# PROC099B_XDS110_Interface_1B.net
KiCad netlist of a schematic drawn in Altium Designer
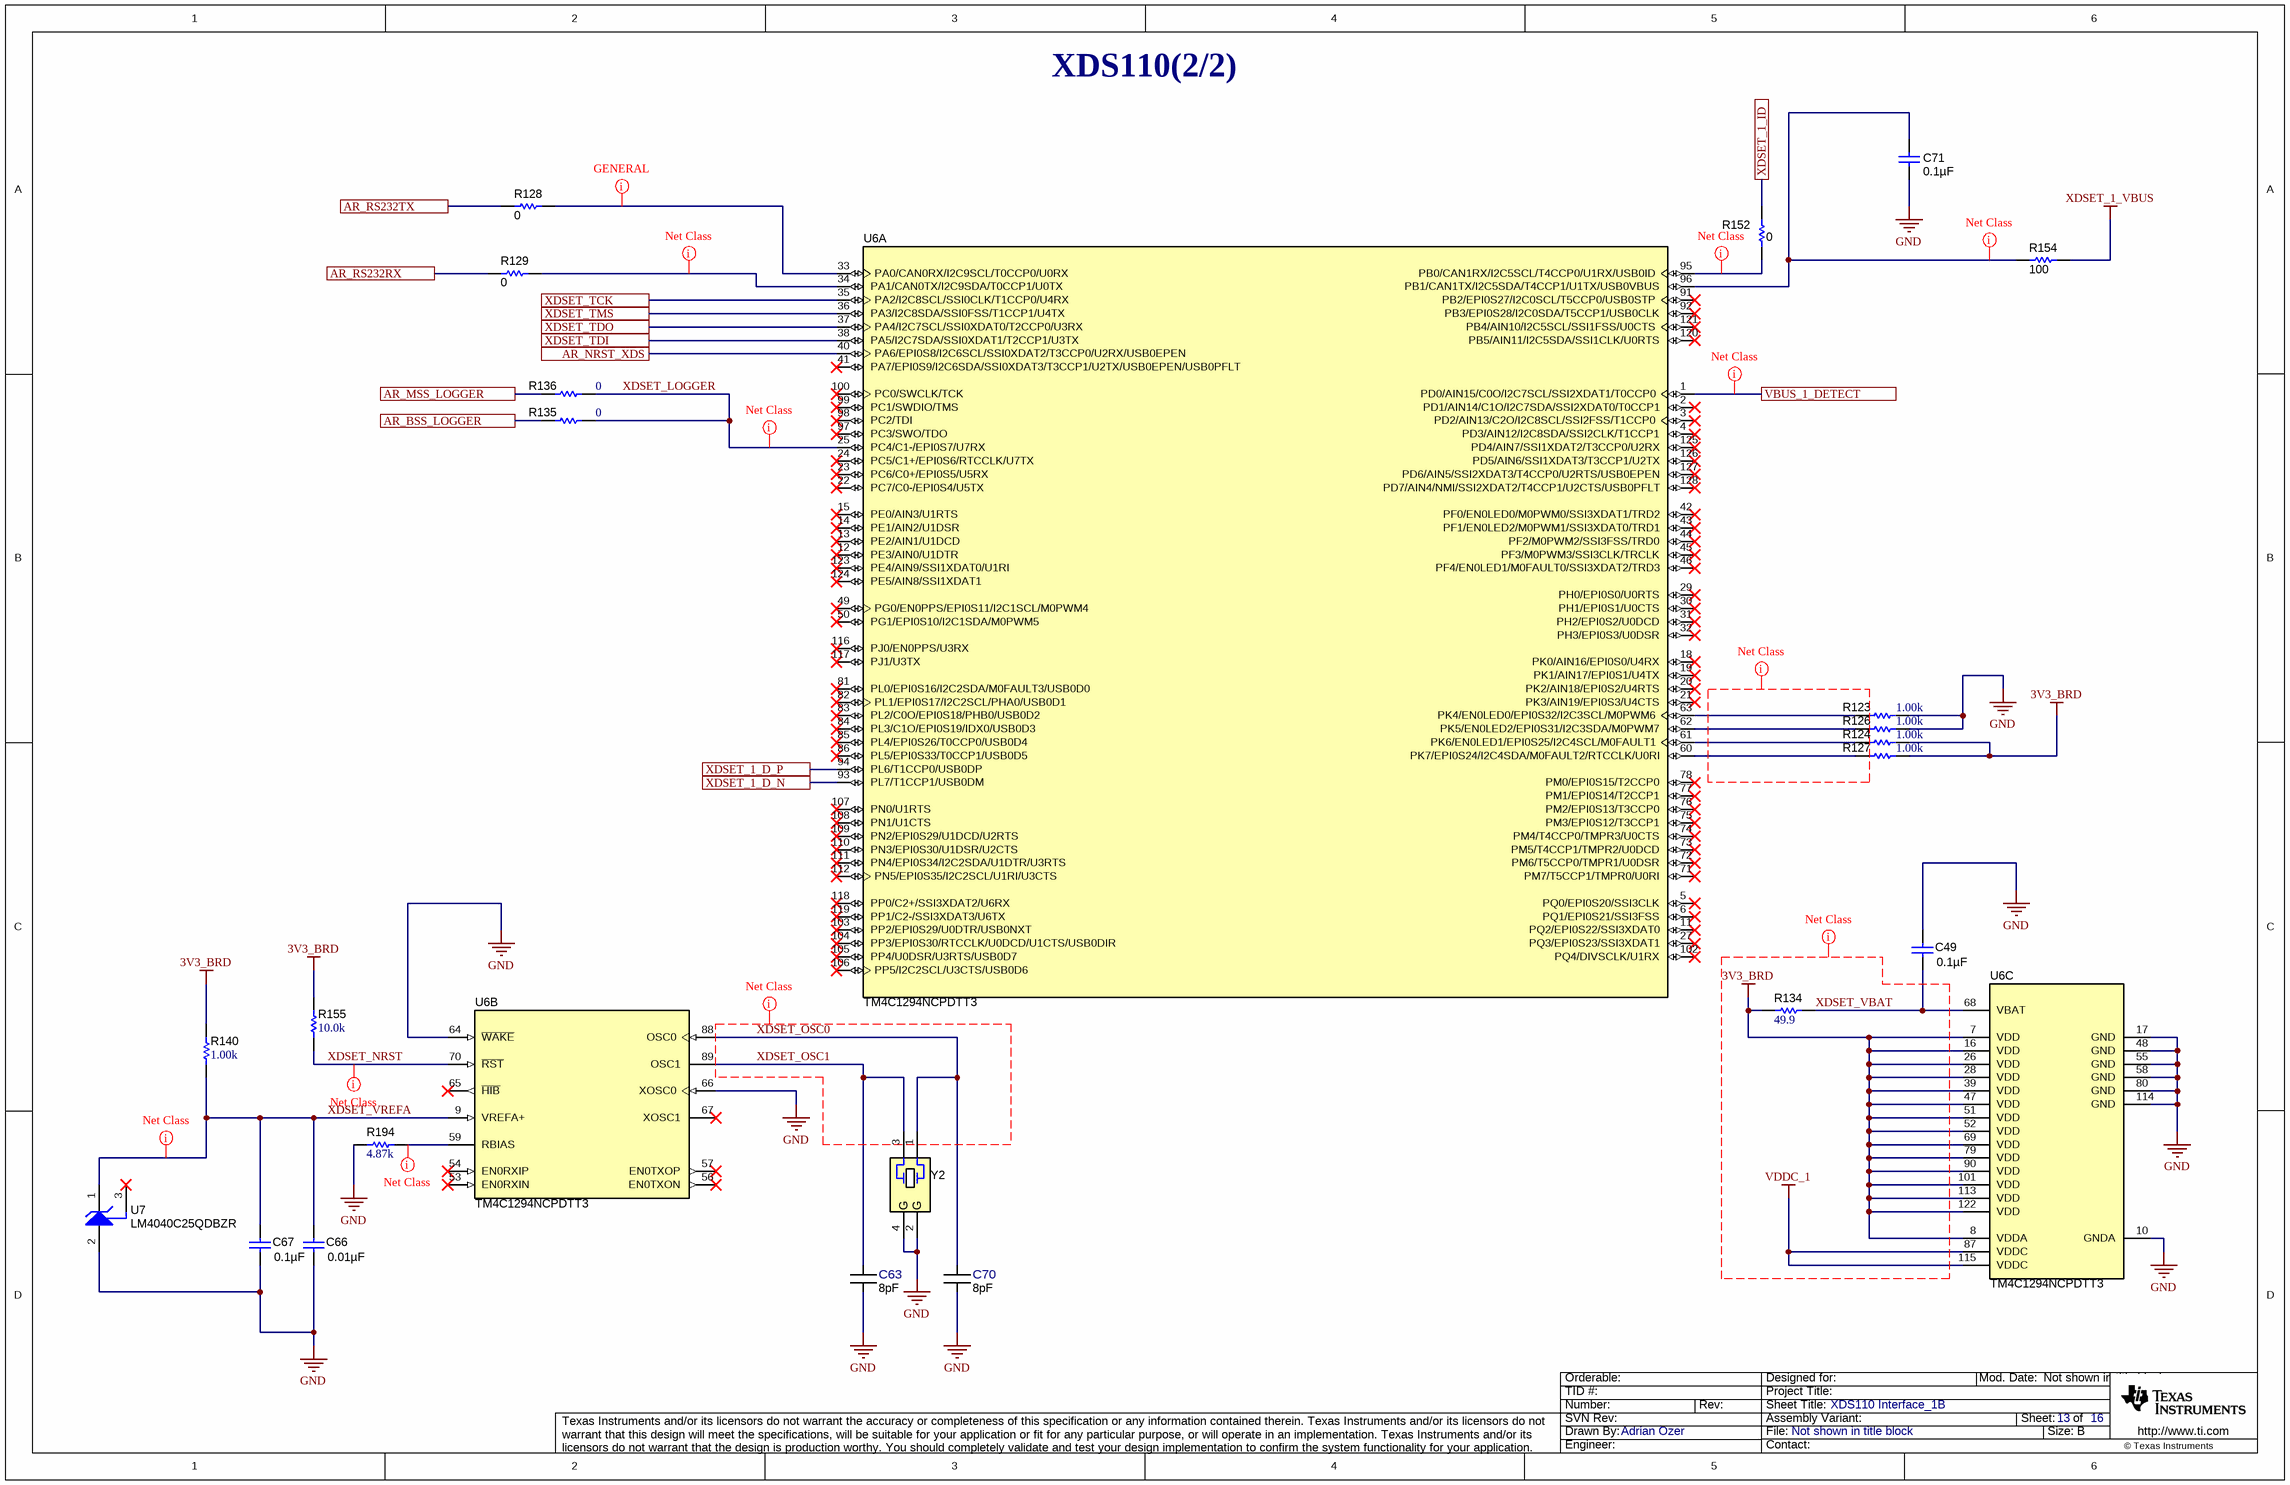
[diagram p0: PROC099B_XDS110 Interface_1B.SchDoc]

(export (version "E")
  (design (tool "Eeschema 10.0.6"))
  (components
    (comp (ref "C49")
      (value "C0402C104K8RACTU")
      (footprint "0402L")
      (description "CAP, CERM, 0.1 µF, 10 V,+/- 10%, X7R, 0402")
      (fields (field (name "MANUFACTURER") "Kemet") (field (name "VALUEDISPLAYED") "0.1µF"))
      (libsource (lib "Altium Vault - TI") (part "CMP-0078241-1"))
    )
    (comp (ref "C63")
      (value "GCM1555C1H8R0DA16D")
      (footprint "FP-GCM1555C1H8R0DA16_0402-MFG")
      (description "Cap Ceramic 8pF 50V C0G 0.5pF SMD 0402 125C Paper T/R")
      (fields (field (name "CAP_F") "8pF") (field (name "MANUFACTURER") "Murata Electronics North America"))
      (libsource (lib "Altium Vault - TI") (part "SYM-B32642B0223J"))
    )
    (comp (ref "C66")
      (value "C0402C103K4RACTU")
      (footprint "0402L")
      (description "CAP, CERM, 0.01 µF, 16 V,+/- 10%, X7R, 0402")
      (fields (field (name "MANUFACTURER") "Kemet") (field (name "VALUEDISPLAYED") "0.01µF"))
      (libsource (lib "Altium Vault - TI") (part "Capacitor"))
    )
    (comp (ref "C67")
      (value "C0402C104K8RACTU")
      (footprint "0402L")
      (description "CAP, CERM, 0.1 µF, 10 V,+/- 10%, X7R, 0402")
      (fields (field (name "MANUFACTURER") "Kemet") (field (name "VALUEDISPLAYED") "0.1µF"))
      (libsource (lib "Altium Vault - TI") (part "Capacitor"))
    )
    (comp (ref "C70")
      (value "GCM1555C1H8R0DA16D")
      (footprint "FP-GCM1555C1H8R0DA16_0402-MFG")
      (description "Cap Ceramic 8pF 50V C0G 0.5pF SMD 0402 125C Paper T/R")
      (fields (field (name "CAP_F") "8pF") (field (name "MANUFACTURER") "Murata Electronics North America"))
      (libsource (lib "Altium Vault - TI") (part "SYM-B32642B0223J"))
    )
    (comp (ref "C71")
      (value "C0402C104K8RACTU")
      (footprint "0402L")
      (description "CAP, CERM, 0.1 µF, 10 V,+/- 10%, X7R, 0402")
      (fields (field (name "MANUFACTURER") "Kemet") (field (name "VALUEDISPLAYED") "0.1µF"))
      (libsource (lib "Altium Vault - TI") (part "Capacitor"))
    )
    (comp (ref "R123")
      (value "CRCW04021K00FKED")
      (footprint "0402L")
      (description "RES, 1.00 k, 1%, 0.063 W, AEC-Q200 Grade 0, 0402")
      (fields (field (name "MANUFACTURER") "Vishay-Dale") (field (name "VALUEDISPLAYED") "1.00k"))
      (libsource (lib "Altium Vault - TI") (part "Resistor"))
    )
    (comp (ref "R124")
      (value "CRCW04021K00FKED")
      (footprint "0402L")
      (description "RES, 1.00 k, 1%, 0.063 W, AEC-Q200 Grade 0, 0402")
      (fields (field (name "MANUFACTURER") "Vishay-Dale") (field (name "VALUEDISPLAYED") "1.00k"))
      (libsource (lib "Altium Vault - TI") (part "Resistor"))
    )
    (comp (ref "R126")
      (value "CRCW04021K00FKED")
      (footprint "0402L")
      (description "RES, 1.00 k, 1%, 0.063 W, AEC-Q200 Grade 0, 0402")
      (fields (field (name "MANUFACTURER") "Vishay-Dale") (field (name "VALUEDISPLAYED") "1.00k"))
      (libsource (lib "Altium Vault - TI") (part "Resistor"))
    )
    (comp (ref "R127")
      (value "CRCW04021K00FKED")
      (footprint "0402L")
      (description "RES, 1.00 k, 1%, 0.063 W, AEC-Q200 Grade 0, 0402")
      (fields (field (name "MANUFACTURER") "Vishay-Dale") (field (name "VALUEDISPLAYED") "1.00k"))
      (libsource (lib "Altium Vault - TI") (part "Resistor"))
    )
    (comp (ref "R128")
      (value "ERJ-2GE0R00X")
      (footprint "0402L")
      (description "RES, 0, 5%, 0.063 W, 0402")
      (fields
        (field (name "MANUFACTURER") "Panasonic")
        (field (name "VALUEDISPLAYED") "0")
        (field (name "PUBLISHER") "Texas Instruments")
      )
      (libsource (lib "Altium Vault - TI") (part "Resistor"))
    )
    (comp (ref "R129")
      (value "ERJ-2GE0R00X")
      (footprint "0402L")
      (description "RES, 0, 5%, 0.063 W, 0402")
      (fields
        (field (name "MANUFACTURER") "Panasonic")
        (field (name "VALUEDISPLAYED") "0")
        (field (name "PUBLISHER") "Texas Instruments")
      )
      (libsource (lib "Altium Vault - TI") (part "Resistor"))
    )
    (comp (ref "R134")
      (value "CRCW040249R9FKED")
      (footprint "0402L")
      (description "RES, 49.9, 1%, 0.063 W, AEC-Q200 Grade 0, 0402")
      (fields (field (name "MANUFACTURER") "Vishay-Dale") (field (name "VALUEDISPLAYED") "49.9"))
      (libsource (lib "Altium Vault - TI") (part "Resistor"))
    )
    (comp (ref "R135")
      (value "CRCW02010000Z0ED")
      (footprint "0201_Silk")
      (description "RES, 0, 5%, 0.05 W, 0201")
      (fields (field (name "MANUFACTURER") "Vishay-Dale") (field (name "VALUEDISPLAYED") "0"))
      (libsource (lib "Altium Vault - TI") (part "Resistor"))
    )
    (comp (ref "R136")
      (value "CRCW02010000Z0ED")
      (footprint "0201_Silk")
      (description "RES, 0, 5%, 0.05 W, 0201")
      (fields (field (name "MANUFACTURER") "Vishay-Dale") (field (name "VALUEDISPLAYED") "0"))
      (libsource (lib "Altium Vault - TI") (part "Resistor"))
    )
    (comp (ref "R140")
      (value "CRCW04021K00FKED")
      (footprint "0402L")
      (description "RES, 1.00 k, 1%, 0.063 W, AEC-Q200 Grade 0, 0402")
      (fields (field (name "MANUFACTURER") "Vishay-Dale") (field (name "VALUEDISPLAYED") "1.00k"))
      (libsource (lib "Altium Vault - TI") (part "Resistor"))
    )
    (comp (ref "R152")
      (value "ERJ-2GE0R00X")
      (footprint "0402L")
      (description "RES, 0, 5%, 0.063 W, 0402")
      (fields
        (field (name "MANUFACTURER") "Panasonic")
        (field (name "VALUEDISPLAYED") "0")
        (field (name "PUBLISHER") "Texas Instruments")
      )
      (libsource (lib "Altium Vault - TI") (part "Resistor"))
    )
    (comp (ref "R154")
      (value "ERJ-2GEJ101X")
      (footprint "0402L")
      (description "RES, 100, 5%, 0.1 W, AEC-Q200 Grade 0, 0402")
      (fields
        (field (name "MANUFACTURER") "Panasonic")
        (field (name "VALUEDISPLAYED") "100")
        (field (name "PUBLISHER") "Texas Instruments")
      )
      (libsource (lib "Altium Vault - TI") (part "Resistor"))
    )
    (comp (ref "R155")
      (value "CRCW040210K0FKED")
      (footprint "0402L")
      (description "RES, 10.0 k, 1%, 0.063 W, AEC-Q200 Grade 0, 0402")
      (fields (field (name "MANUFACTURER") "Vishay-Dale") (field (name "VALUEDISPLAYED") "10.0k"))
      (libsource (lib "Altium Vault - TI") (part "Resistor"))
    )
    (comp (ref "R194")
      (value "CRCW04024K87FKED")
      (footprint "0402L")
      (description "RES, 4.87 k, 1%, 0.063 W, AEC-Q200 Grade 0, 0402")
      (fields (field (name "MANUFACTURER") "Vishay-Dale") (field (name "VALUEDISPLAYED") "4.87k"))
      (libsource (lib "Altium Vault - TI") (part "Resistor"))
    )
    (comp (ref "U6")
      (value "TM4C1294NCPDTT3")
      (footprint "PDT0128A")
      (fields (field (name "PARTNUMBER") "TM4C1294NCPDTT3") (field (name "MANUFACTURER") "Texas Instruments"))
      (libsource (lib "Altium Vault - TI") (part "TI-TM4C1294NCPDT-128"))
    )
    (comp (ref "U7")
      (value "LM4040C25QDBZR")
      (footprint "DBZ0003A_N")
      (fields (field (name "MANUFACTURER") "Texas Instruments") (field (name "PARTNUMBER") "LM4040C25QDBZR"))
      (libsource (lib "Altium Vault - TI") (part "TI-LM4040C25DBZ3"))
    )
    (comp (ref "Y2")
      (value "NX3225SA-16.000M-STD-CRS-2")
      (footprint "NDK_NX3225SA")
      (description "Crystal, 16 MHz, 15 ppm, 8 pF, AEC-Q200 Grade 1, SMD")
      (fields (field (name "MANUFACTURER") "NDK"))
      (libsource (lib "Altium Vault - TI") (part "CMP-0078214-2"))
    )
  )
  (nets
    (net (code "1") (name "/AR_BSS_LOGGER") (class "Default")
      (node (ref "R135") (pin "1") (pinfunction "1_1") (pintype "passive"))
    )
    (net (code "2") (name "/AR_MSS_LOGGER") (class "Default")
      (node (ref "R136") (pin "1") (pinfunction "1_1") (pintype "passive"))
    )
    (net (code "3") (name "/AR_NRST_XDS") (class "Default")
      (node (ref "U6") (pin "40") (pinfunction "PA6/EPI0S8/I2C6SCL/SSI0XDAT2/T3CCP0/U2RX/USB0EPEN_40") (pintype "bidirectional"))
    )
    (net (code "4") (name "/AR_RS232RX") (class "Default")
      (node (ref "R129") (pin "1") (pinfunction "1_1") (pintype "passive"))
    )
    (net (code "5") (name "/AR_RS232TX") (class "Default")
      (node (ref "R128") (pin "1") (pinfunction "1_1") (pintype "passive"))
    )
    (net (code "6") (name "/VBUS_1_DETECT") (class "Default")
      (node (ref "U6") (pin "1") (pinfunction "PD0/AIN15/C0O/I2C7SCL/SSI2XDAT1/T0CCP0_1") (pintype "bidirectional"))
    )
    (net (code "7") (name "/XDSET_1_D_N") (class "Default")
      (node (ref "U6") (pin "93") (pinfunction "PL7/T1CCP1/USB0DM_93") (pintype "bidirectional"))
    )
    (net (code "8") (name "/XDSET_1_D_P") (class "Default")
      (node (ref "U6") (pin "94") (pinfunction "PL6/T1CCP0/USB0DP_94") (pintype "bidirectional"))
    )
    (net (code "9") (name "/XDSET_1_ID") (class "Default")
      (node (ref "R152") (pin "2") (pinfunction "2_2") (pintype "passive"))
    )
    (net (code "10") (name "/XDSET_LOGGER") (class "Default")
      (node (ref "R135") (pin "2") (pinfunction "2_2") (pintype "passive"))
      (node (ref "R136") (pin "2") (pinfunction "2_2") (pintype "passive"))
      (node (ref "U6") (pin "25") (pinfunction "PC4/C1-/EPI0S7/U7RX_25") (pintype "bidirectional"))
    )
    (net (code "11") (name "/XDSET_NRST") (class "Default")
      (node (ref "R155") (pin "1") (pinfunction "1_1") (pintype "passive"))
      (node (ref "U6") (pin "70") (pinfunction "~{RST}_70") (pintype "input"))
    )
    (net (code "12") (name "/XDSET_OSC0") (class "Default")
      (node (ref "C70") (pin "1") (pinfunction "1_1") (pintype "passive"))
      (node (ref "U6") (pin "88") (pinfunction "OSC0_88") (pintype "input"))
      (node (ref "Y2") (pin "1") (pinfunction "1_1") (pintype "passive"))
    )
    (net (code "13") (name "/XDSET_OSC1") (class "Default")
      (node (ref "C63") (pin "1") (pinfunction "1_1") (pintype "passive"))
      (node (ref "U6") (pin "89") (pinfunction "OSC1_89") (pintype "passive"))
      (node (ref "Y2") (pin "3") (pinfunction "3_3") (pintype "passive"))
    )
    (net (code "14") (name "/XDSET_TCK") (class "Default")
      (node (ref "U6") (pin "35") (pinfunction "PA2/I2C8SCL/SSI0CLK/T1CCP0/U4RX_35") (pintype "bidirectional"))
    )
    (net (code "15") (name "/XDSET_TDI") (class "Default")
      (node (ref "U6") (pin "38") (pinfunction "PA5/I2C7SDA/SSI0XDAT1/T2CCP1/U3TX_38") (pintype "bidirectional"))
    )
    (net (code "16") (name "/XDSET_TDO") (class "Default")
      (node (ref "U6") (pin "37") (pinfunction "PA4/I2C7SCL/SSI0XDAT0/T2CCP0/U3RX_37") (pintype "bidirectional"))
    )
    (net (code "17") (name "/XDSET_TMS") (class "Default")
      (node (ref "U6") (pin "36") (pinfunction "PA3/I2C8SDA/SSI0FSS/T1CCP1/U4TX_36") (pintype "bidirectional"))
    )
    (net (code "18") (name "/XDSET_VBAT") (class "Default")
      (node (ref "C49") (pin "2") (pinfunction "2_2") (pintype "passive"))
      (node (ref "R134") (pin "1") (pinfunction "1_1") (pintype "passive"))
      (node (ref "U6") (pin "68") (pinfunction "VBAT_68") (pintype "power_in"))
    )
    (net (code "19") (name "/XDSET_VREFA") (class "Default")
      (node (ref "C66") (pin "2") (pinfunction "2_2") (pintype "passive"))
      (node (ref "C67") (pin "2") (pinfunction "2_2") (pintype "passive"))
      (node (ref "R140") (pin "1") (pinfunction "1_1") (pintype "passive"))
      (node (ref "U6") (pin "9") (pinfunction "VREFA+_9") (pintype "input"))
      (node (ref "U7") (pin "1") (pinfunction "CATHODE_1") (pintype "passive"))
    )
    (net (code "20") (name "3V3_BRD") (class "Default")
      (node (ref "R124") (pin "2") (pinfunction "2_2") (pintype "passive"))
      (node (ref "R127") (pin "2") (pinfunction "2_2") (pintype "passive"))
      (node (ref "R134") (pin "2") (pinfunction "2_2") (pintype "passive"))
      (node (ref "R140") (pin "2") (pinfunction "2_2") (pintype "passive"))
      (node (ref "R155") (pin "2") (pinfunction "2_2") (pintype "passive"))
      (node (ref "U6") (pin "101") (pinfunction "VDD_101") (pintype "power_in"))
      (node (ref "U6") (pin "113") (pinfunction "VDD_113") (pintype "power_in"))
      (node (ref "U6") (pin "122") (pinfunction "VDD_122") (pintype "power_in"))
      (node (ref "U6") (pin "16") (pinfunction "VDD_16") (pintype "power_in"))
      (node (ref "U6") (pin "26") (pinfunction "VDD_26") (pintype "power_in"))
      (node (ref "U6") (pin "28") (pinfunction "VDD_28") (pintype "power_in"))
      (node (ref "U6") (pin "39") (pinfunction "VDD_39") (pintype "power_in"))
      (node (ref "U6") (pin "47") (pinfunction "VDD_47") (pintype "power_in"))
      (node (ref "U6") (pin "51") (pinfunction "VDD_51") (pintype "power_in"))
      (node (ref "U6") (pin "52") (pinfunction "VDD_52") (pintype "power_in"))
      (node (ref "U6") (pin "69") (pinfunction "VDD_69") (pintype "power_in"))
      (node (ref "U6") (pin "7") (pinfunction "VDD_7") (pintype "power_in"))
      (node (ref "U6") (pin "79") (pinfunction "VDD_79") (pintype "power_in"))
      (node (ref "U6") (pin "8") (pinfunction "VDDA_8") (pintype "power_in"))
      (node (ref "U6") (pin "90") (pinfunction "VDD_90") (pintype "power_in"))
    )
    (net (code "21") (name "GND") (class "Default")
      (node (ref "C49") (pin "1") (pinfunction "1_1") (pintype "passive"))
      (node (ref "C63") (pin "2") (pinfunction "2_2") (pintype "passive"))
      (node (ref "C66") (pin "1") (pinfunction "1_1") (pintype "passive"))
      (node (ref "C67") (pin "1") (pinfunction "1_1") (pintype "passive"))
      (node (ref "C70") (pin "2") (pinfunction "2_2") (pintype "passive"))
      (node (ref "C71") (pin "1") (pinfunction "1_1") (pintype "passive"))
      (node (ref "R123") (pin "2") (pinfunction "2_2") (pintype "passive"))
      (node (ref "R126") (pin "2") (pinfunction "2_2") (pintype "passive"))
      (node (ref "R194") (pin "1") (pinfunction "1_1") (pintype "passive"))
      (node (ref "U6") (pin "10") (pinfunction "GNDA_10") (pintype "power_in"))
      (node (ref "U6") (pin "114") (pinfunction "GND_114") (pintype "power_in"))
      (node (ref "U6") (pin "17") (pinfunction "GND_17") (pintype "power_in"))
      (node (ref "U6") (pin "48") (pinfunction "GND_48") (pintype "power_in"))
      (node (ref "U6") (pin "55") (pinfunction "GND_55") (pintype "power_in"))
      (node (ref "U6") (pin "58") (pinfunction "GND_58") (pintype "power_in"))
      (node (ref "U6") (pin "64") (pinfunction "~{WAKE}_64") (pintype "input"))
      (node (ref "U6") (pin "66") (pinfunction "XOSC0_66") (pintype "input"))
      (node (ref "U6") (pin "80") (pinfunction "GND_80") (pintype "power_in"))
      (node (ref "U7") (pin "2") (pinfunction "ANODE_2") (pintype "passive"))
      (node (ref "Y2") (pin "2") (pinfunction "GND_2") (pintype "power_in"))
      (node (ref "Y2") (pin "4") (pinfunction "GND_4") (pintype "power_in"))
    )
    (net (code "22") (name "Net-(U6A-PA0{slash}CAN0RX{slash}I2C9SCL{slash}T0CCP0{slash}U0RX)") (class "Default")
      (node (ref "R128") (pin "2") (pinfunction "2_2") (pintype "passive"))
      (node (ref "U6") (pin "33") (pinfunction "PA0/CAN0RX/I2C9SCL/T0CCP0/U0RX_33") (pintype "bidirectional"))
    )
    (net (code "23") (name "Net-(U6A-PA1{slash}CAN0TX{slash}I2C9SDA{slash}T0CCP1{slash}U0TX)") (class "Default")
      (node (ref "R129") (pin "2") (pinfunction "2_2") (pintype "passive"))
      (node (ref "U6") (pin "34") (pinfunction "PA1/CAN0TX/I2C9SDA/T0CCP1/U0TX_34") (pintype "bidirectional"))
    )
    (net (code "24") (name "Net-(U6A-PB0{slash}CAN1RX{slash}I2C5SCL{slash}T4CCP0{slash}U1RX{slash}USB0ID)") (class "Default")
      (node (ref "R152") (pin "1") (pinfunction "1_1") (pintype "passive"))
      (node (ref "U6") (pin "95") (pinfunction "PB0/CAN1RX/I2C5SCL/T4CCP0/U1RX/USB0ID_95") (pintype "bidirectional"))
    )
    (net (code "25") (name "Net-(U6A-PB1{slash}CAN1TX{slash}I2C5SDA{slash}T4CCP1{slash}U1TX{slash}USB0VBUS)") (class "Default")
      (node (ref "C71") (pin "2") (pinfunction "2_2") (pintype "passive"))
      (node (ref "R154") (pin "1") (pinfunction "1_1") (pintype "passive"))
      (node (ref "U6") (pin "96") (pinfunction "PB1/CAN1TX/I2C5SDA/T4CCP1/U1TX/USB0VBUS_96") (pintype "bidirectional"))
    )
    (net (code "26") (name "Net-(U6A-PK4{slash}EN0LED0{slash}EPI0S32{slash}I2C3SCL{slash}M0PWM6)") (class "Default")
      (node (ref "R123") (pin "1") (pinfunction "1_1") (pintype "passive"))
      (node (ref "U6") (pin "63") (pinfunction "PK4/EN0LED0/EPI0S32/I2C3SCL/M0PWM6_63") (pintype "bidirectional"))
    )
    (net (code "27") (name "Net-(U6A-PK5{slash}EN0LED2{slash}EPI0S31{slash}I2C3SDA{slash}M0PWM7)") (class "Default")
      (node (ref "R126") (pin "1") (pinfunction "1_1") (pintype "passive"))
      (node (ref "U6") (pin "62") (pinfunction "PK5/EN0LED2/EPI0S31/I2C3SDA/M0PWM7_62") (pintype "bidirectional"))
    )
    (net (code "28") (name "Net-(U6A-PK6{slash}EN0LED1{slash}EPI0S25{slash}I2C4SCL{slash}M0FAULT1)") (class "Default")
      (node (ref "R124") (pin "1") (pinfunction "1_1") (pintype "passive"))
      (node (ref "U6") (pin "61") (pinfunction "PK6/EN0LED1/EPI0S25/I2C4SCL/M0FAULT1_61") (pintype "bidirectional"))
    )
    (net (code "29") (name "Net-(U6A-PK7{slash}EPI0S24{slash}I2C4SDA{slash}M0FAULT2{slash}RTCCLK{slash}U0RI)") (class "Default")
      (node (ref "R127") (pin "1") (pinfunction "1_1") (pintype "passive"))
      (node (ref "U6") (pin "60") (pinfunction "PK7/EPI0S24/I2C4SDA/M0FAULT2/RTCCLK/U0RI_60") (pintype "bidirectional"))
    )
    (net (code "30") (name "Net-(U6B-RBIAS)") (class "Default")
      (node (ref "R194") (pin "2") (pinfunction "2_2") (pintype "passive"))
      (node (ref "U6") (pin "59") (pinfunction "RBIAS_59") (pintype "passive"))
    )
    (net (code "31") (name "VDDC_1") (class "Default")
      (node (ref "U6") (pin "115") (pinfunction "VDDC_115") (pintype "power_in"))
      (node (ref "U6") (pin "87") (pinfunction "VDDC_87") (pintype "power_in"))
    )
    (net (code "32") (name "XDSET_1_VBUS") (class "Default")
      (node (ref "R154") (pin "2") (pinfunction "2_2") (pintype "passive"))
    )
    (net (code "33") (name "unconnected-(U6A-PA7{slash}EPI0S9{slash}I2C6SDA{slash}SSI0XDAT3{slash}T3CCP1{slash}U2TX{slash}USB0EPEN{slash}USB0PFLT-Pad41)") (class "Default")
      (node (ref "U6") (pin "41") (pinfunction "PA7/EPI0S9/I2C6SDA/SSI0XDAT3/T3CCP1/U2TX/USB0EPEN/USB0PFLT_41") (pintype "bidirectional+no_connect"))
    )
    (net (code "34") (name "unconnected-(U6A-PB2{slash}EPI0S27{slash}I2C0SCL{slash}T5CCP0{slash}USB0STP-Pad91)") (class "Default")
      (node (ref "U6") (pin "91") (pinfunction "PB2/EPI0S27/I2C0SCL/T5CCP0/USB0STP_91") (pintype "bidirectional+no_connect"))
    )
    (net (code "35") (name "unconnected-(U6A-PB3{slash}EPI0S28{slash}I2C0SDA{slash}T5CCP1{slash}USB0CLK-Pad92)") (class "Default")
      (node (ref "U6") (pin "92") (pinfunction "PB3/EPI0S28/I2C0SDA/T5CCP1/USB0CLK_92") (pintype "bidirectional+no_connect"))
    )
    (net (code "36") (name "unconnected-(U6A-PB4{slash}AIN10{slash}I2C5SCL{slash}SSI1FSS{slash}U0CTS-Pad121)") (class "Default")
      (node (ref "U6") (pin "121") (pinfunction "PB4/AIN10/I2C5SCL/SSI1FSS/U0CTS_121") (pintype "bidirectional+no_connect"))
    )
    (net (code "37") (name "unconnected-(U6A-PB5{slash}AIN11{slash}I2C5SDA{slash}SSI1CLK{slash}U0RTS-Pad120)") (class "Default")
      (node (ref "U6") (pin "120") (pinfunction "PB5/AIN11/I2C5SDA/SSI1CLK/U0RTS_120") (pintype "bidirectional+no_connect"))
    )
    (net (code "38") (name "unconnected-(U6A-PC0{slash}SWCLK{slash}TCK-Pad100)") (class "Default")
      (node (ref "U6") (pin "100") (pinfunction "PC0/SWCLK/TCK_100") (pintype "bidirectional+no_connect"))
    )
    (net (code "39") (name "unconnected-(U6A-PC1{slash}SWDIO{slash}TMS-Pad99)") (class "Default")
      (node (ref "U6") (pin "99") (pinfunction "PC1/SWDIO/TMS_99") (pintype "bidirectional+no_connect"))
    )
    (net (code "40") (name "unconnected-(U6A-PC2{slash}TDI-Pad98)") (class "Default")
      (node (ref "U6") (pin "98") (pinfunction "PC2/TDI_98") (pintype "bidirectional+no_connect"))
    )
    (net (code "41") (name "unconnected-(U6A-PC3{slash}SWO{slash}TDO-Pad97)") (class "Default")
      (node (ref "U6") (pin "97") (pinfunction "PC3/SWO/TDO_97") (pintype "bidirectional+no_connect"))
    )
    (net (code "42") (name "unconnected-(U6A-PC5{slash}C1+{slash}EPI0S6{slash}RTCCLK{slash}U7TX-Pad24)") (class "Default")
      (node (ref "U6") (pin "24") (pinfunction "PC5/C1+/EPI0S6/RTCCLK/U7TX_24") (pintype "bidirectional+no_connect"))
    )
    (net (code "43") (name "unconnected-(U6A-PC6{slash}C0+{slash}EPI0S5{slash}U5RX-Pad23)") (class "Default")
      (node (ref "U6") (pin "23") (pinfunction "PC6/C0+/EPI0S5/U5RX_23") (pintype "bidirectional+no_connect"))
    )
    (net (code "44") (name "unconnected-(U6A-PC7{slash}C0-{slash}EPI0S4{slash}U5TX-Pad22)") (class "Default")
      (node (ref "U6") (pin "22") (pinfunction "PC7/C0-/EPI0S4/U5TX_22") (pintype "bidirectional+no_connect"))
    )
    (net (code "45") (name "unconnected-(U6A-PD1{slash}AIN14{slash}C1O{slash}I2C7SDA{slash}SSI2XDAT0{slash}T0CCP1-Pad2)") (class "Default")
      (node (ref "U6") (pin "2") (pinfunction "PD1/AIN14/C1O/I2C7SDA/SSI2XDAT0/T0CCP1_2") (pintype "bidirectional+no_connect"))
    )
    (net (code "46") (name "unconnected-(U6A-PD2{slash}AIN13{slash}C2O{slash}I2C8SCL{slash}SSI2FSS{slash}T1CCP0-Pad3)") (class "Default")
      (node (ref "U6") (pin "3") (pinfunction "PD2/AIN13/C2O/I2C8SCL/SSI2FSS/T1CCP0_3") (pintype "bidirectional+no_connect"))
    )
    (net (code "47") (name "unconnected-(U6A-PD3{slash}AIN12{slash}I2C8SDA{slash}SSI2CLK{slash}T1CCP1-Pad4)") (class "Default")
      (node (ref "U6") (pin "4") (pinfunction "PD3/AIN12/I2C8SDA/SSI2CLK/T1CCP1_4") (pintype "bidirectional+no_connect"))
    )
    (net (code "48") (name "unconnected-(U6A-PD4{slash}AIN7{slash}SSI1XDAT2{slash}T3CCP0{slash}U2RX-Pad125)") (class "Default")
      (node (ref "U6") (pin "125") (pinfunction "PD4/AIN7/SSI1XDAT2/T3CCP0/U2RX_125") (pintype "bidirectional+no_connect"))
    )
    (net (code "49") (name "unconnected-(U6A-PD5{slash}AIN6{slash}SSI1XDAT3{slash}T3CCP1{slash}U2TX-Pad126)") (class "Default")
      (node (ref "U6") (pin "126") (pinfunction "PD5/AIN6/SSI1XDAT3/T3CCP1/U2TX_126") (pintype "bidirectional+no_connect"))
    )
    (net (code "50") (name "unconnected-(U6A-PD6{slash}AIN5{slash}SSI2XDAT3{slash}T4CCP0{slash}U2RTS{slash}USB0EPEN-Pad127)") (class "Default")
      (node (ref "U6") (pin "127") (pinfunction "PD6/AIN5/SSI2XDAT3/T4CCP0/U2RTS/USB0EPEN_127") (pintype "bidirectional+no_connect"))
    )
    (net (code "51") (name "unconnected-(U6A-PD7{slash}AIN4{slash}NMI{slash}SSI2XDAT2{slash}T4CCP1{slash}U2CTS{slash}USB0PFLT-Pad128)") (class "Default")
      (node (ref "U6") (pin "128") (pinfunction "PD7/AIN4/NMI/SSI2XDAT2/T4CCP1/U2CTS/USB0PFLT_128") (pintype "bidirectional+no_connect"))
    )
    (net (code "52") (name "unconnected-(U6A-PE0{slash}AIN3{slash}U1RTS-Pad15)") (class "Default")
      (node (ref "U6") (pin "15") (pinfunction "PE0/AIN3/U1RTS_15") (pintype "bidirectional+no_connect"))
    )
    (net (code "53") (name "unconnected-(U6A-PE1{slash}AIN2{slash}U1DSR-Pad14)") (class "Default")
      (node (ref "U6") (pin "14") (pinfunction "PE1/AIN2/U1DSR_14") (pintype "bidirectional+no_connect"))
    )
    (net (code "54") (name "unconnected-(U6A-PE2{slash}AIN1{slash}U1DCD-Pad13)") (class "Default")
      (node (ref "U6") (pin "13") (pinfunction "PE2/AIN1/U1DCD_13") (pintype "bidirectional+no_connect"))
    )
    (net (code "55") (name "unconnected-(U6A-PE3{slash}AIN0{slash}U1DTR-Pad12)") (class "Default")
      (node (ref "U6") (pin "12") (pinfunction "PE3/AIN0/U1DTR_12") (pintype "bidirectional+no_connect"))
    )
    (net (code "56") (name "unconnected-(U6A-PE4{slash}AIN9{slash}SSI1XDAT0{slash}U1RI-Pad123)") (class "Default")
      (node (ref "U6") (pin "123") (pinfunction "PE4/AIN9/SSI1XDAT0/U1RI_123") (pintype "bidirectional+no_connect"))
    )
    (net (code "57") (name "unconnected-(U6A-PE5{slash}AIN8{slash}SSI1XDAT1-Pad124)") (class "Default")
      (node (ref "U6") (pin "124") (pinfunction "PE5/AIN8/SSI1XDAT1_124") (pintype "bidirectional+no_connect"))
    )
    (net (code "58") (name "unconnected-(U6A-PF0{slash}EN0LED0{slash}M0PWM0{slash}SSI3XDAT1{slash}TRD2-Pad42)") (class "Default")
      (node (ref "U6") (pin "42") (pinfunction "PF0/EN0LED0/M0PWM0/SSI3XDAT1/TRD2_42") (pintype "bidirectional+no_connect"))
    )
    (net (code "59") (name "unconnected-(U6A-PF1{slash}EN0LED2{slash}M0PWM1{slash}SSI3XDAT0{slash}TRD1-Pad43)") (class "Default")
      (node (ref "U6") (pin "43") (pinfunction "PF1/EN0LED2/M0PWM1/SSI3XDAT0/TRD1_43") (pintype "bidirectional+no_connect"))
    )
    (net (code "60") (name "unconnected-(U6A-PF2{slash}M0PWM2{slash}SSI3FSS{slash}TRD0-Pad44)") (class "Default")
      (node (ref "U6") (pin "44") (pinfunction "PF2/M0PWM2/SSI3FSS/TRD0_44") (pintype "bidirectional+no_connect"))
    )
    (net (code "61") (name "unconnected-(U6A-PF3{slash}M0PWM3{slash}SSI3CLK{slash}TRCLK-Pad45)") (class "Default")
      (node (ref "U6") (pin "45") (pinfunction "PF3/M0PWM3/SSI3CLK/TRCLK_45") (pintype "bidirectional+no_connect"))
    )
    (net (code "62") (name "unconnected-(U6A-PF4{slash}EN0LED1{slash}M0FAULT0{slash}SSI3XDAT2{slash}TRD3-Pad46)") (class "Default")
      (node (ref "U6") (pin "46") (pinfunction "PF4/EN0LED1/M0FAULT0/SSI3XDAT2/TRD3_46") (pintype "bidirectional+no_connect"))
    )
    (net (code "63") (name "unconnected-(U6A-PG0{slash}EN0PPS{slash}EPI0S11{slash}I2C1SCL{slash}M0PWM4-Pad49)") (class "Default")
      (node (ref "U6") (pin "49") (pinfunction "PG0/EN0PPS/EPI0S11/I2C1SCL/M0PWM4_49") (pintype "bidirectional+no_connect"))
    )
    (net (code "64") (name "unconnected-(U6A-PG1{slash}EPI0S10{slash}I2C1SDA{slash}M0PWM5-Pad50)") (class "Default")
      (node (ref "U6") (pin "50") (pinfunction "PG1/EPI0S10/I2C1SDA/M0PWM5_50") (pintype "bidirectional+no_connect"))
    )
    (net (code "65") (name "unconnected-(U6A-PH0{slash}EPI0S0{slash}U0RTS-Pad29)") (class "Default")
      (node (ref "U6") (pin "29") (pinfunction "PH0/EPI0S0/U0RTS_29") (pintype "bidirectional+no_connect"))
    )
    (net (code "66") (name "unconnected-(U6A-PH1{slash}EPI0S1{slash}U0CTS-Pad30)") (class "Default")
      (node (ref "U6") (pin "30") (pinfunction "PH1/EPI0S1/U0CTS_30") (pintype "bidirectional+no_connect"))
    )
    (net (code "67") (name "unconnected-(U6A-PH2{slash}EPI0S2{slash}U0DCD-Pad31)") (class "Default")
      (node (ref "U6") (pin "31") (pinfunction "PH2/EPI0S2/U0DCD_31") (pintype "bidirectional+no_connect"))
    )
    (net (code "68") (name "unconnected-(U6A-PH3{slash}EPI0S3{slash}U0DSR-Pad32)") (class "Default")
      (node (ref "U6") (pin "32") (pinfunction "PH3/EPI0S3/U0DSR_32") (pintype "bidirectional+no_connect"))
    )
    (net (code "69") (name "unconnected-(U6A-PJ0{slash}EN0PPS{slash}U3RX-Pad116)") (class "Default")
      (node (ref "U6") (pin "116") (pinfunction "PJ0/EN0PPS/U3RX_116") (pintype "bidirectional+no_connect"))
    )
    (net (code "70") (name "unconnected-(U6A-PJ1{slash}U3TX-Pad117)") (class "Default")
      (node (ref "U6") (pin "117") (pinfunction "PJ1/U3TX_117") (pintype "bidirectional+no_connect"))
    )
    (net (code "71") (name "unconnected-(U6A-PK0{slash}AIN16{slash}EPI0S0{slash}U4RX-Pad18)") (class "Default")
      (node (ref "U6") (pin "18") (pinfunction "PK0/AIN16/EPI0S0/U4RX_18") (pintype "bidirectional+no_connect"))
    )
    (net (code "72") (name "unconnected-(U6A-PK1{slash}AIN17{slash}EPI0S1{slash}U4TX-Pad19)") (class "Default")
      (node (ref "U6") (pin "19") (pinfunction "PK1/AIN17/EPI0S1/U4TX_19") (pintype "bidirectional+no_connect"))
    )
    (net (code "73") (name "unconnected-(U6A-PK2{slash}AIN18{slash}EPI0S2{slash}U4RTS-Pad20)") (class "Default")
      (node (ref "U6") (pin "20") (pinfunction "PK2/AIN18/EPI0S2/U4RTS_20") (pintype "bidirectional+no_connect"))
    )
    (net (code "74") (name "unconnected-(U6A-PK3{slash}AIN19{slash}EPI0S3{slash}U4CTS-Pad21)") (class "Default")
      (node (ref "U6") (pin "21") (pinfunction "PK3/AIN19/EPI0S3/U4CTS_21") (pintype "bidirectional+no_connect"))
    )
    (net (code "75") (name "unconnected-(U6A-PL0{slash}EPI0S16{slash}I2C2SDA{slash}M0FAULT3{slash}USB0D0-Pad81)") (class "Default")
      (node (ref "U6") (pin "81") (pinfunction "PL0/EPI0S16/I2C2SDA/M0FAULT3/USB0D0_81") (pintype "bidirectional+no_connect"))
    )
    (net (code "76") (name "unconnected-(U6A-PL1{slash}EPI0S17{slash}I2C2SCL{slash}PHA0{slash}USB0D1-Pad82)") (class "Default")
      (node (ref "U6") (pin "82") (pinfunction "PL1/EPI0S17/I2C2SCL/PHA0/USB0D1_82") (pintype "bidirectional+no_connect"))
    )
    (net (code "77") (name "unconnected-(U6A-PL2{slash}C0O{slash}EPI0S18{slash}PHB0{slash}USB0D2-Pad83)") (class "Default")
      (node (ref "U6") (pin "83") (pinfunction "PL2/C0O/EPI0S18/PHB0/USB0D2_83") (pintype "bidirectional+no_connect"))
    )
    (net (code "78") (name "unconnected-(U6A-PL3{slash}C1O{slash}EPI0S19{slash}IDX0{slash}USB0D3-Pad84)") (class "Default")
      (node (ref "U6") (pin "84") (pinfunction "PL3/C1O/EPI0S19/IDX0/USB0D3_84") (pintype "bidirectional+no_connect"))
    )
    (net (code "79") (name "unconnected-(U6A-PL4{slash}EPI0S26{slash}T0CCP0{slash}USB0D4-Pad85)") (class "Default")
      (node (ref "U6") (pin "85") (pinfunction "PL4/EPI0S26/T0CCP0/USB0D4_85") (pintype "bidirectional+no_connect"))
    )
    (net (code "80") (name "unconnected-(U6A-PL5{slash}EPI0S33{slash}T0CCP1{slash}USB0D5-Pad86)") (class "Default")
      (node (ref "U6") (pin "86") (pinfunction "PL5/EPI0S33/T0CCP1/USB0D5_86") (pintype "bidirectional+no_connect"))
    )
    (net (code "81") (name "unconnected-(U6A-PM0{slash}EPI0S15{slash}T2CCP0-Pad78)") (class "Default")
      (node (ref "U6") (pin "78") (pinfunction "PM0/EPI0S15/T2CCP0_78") (pintype "bidirectional+no_connect"))
    )
    (net (code "82") (name "unconnected-(U6A-PM1{slash}EPI0S14{slash}T2CCP1-Pad77)") (class "Default")
      (node (ref "U6") (pin "77") (pinfunction "PM1/EPI0S14/T2CCP1_77") (pintype "bidirectional+no_connect"))
    )
    (net (code "83") (name "unconnected-(U6A-PM2{slash}EPI0S13{slash}T3CCP0-Pad76)") (class "Default")
      (node (ref "U6") (pin "76") (pinfunction "PM2/EPI0S13/T3CCP0_76") (pintype "bidirectional+no_connect"))
    )
    (net (code "84") (name "unconnected-(U6A-PM3{slash}EPI0S12{slash}T3CCP1-Pad75)") (class "Default")
      (node (ref "U6") (pin "75") (pinfunction "PM3/EPI0S12/T3CCP1_75") (pintype "bidirectional+no_connect"))
    )
    (net (code "85") (name "unconnected-(U6A-PM4{slash}T4CCP0{slash}TMPR3{slash}U0CTS-Pad74)") (class "Default")
      (node (ref "U6") (pin "74") (pinfunction "PM4/T4CCP0/TMPR3/U0CTS_74") (pintype "bidirectional+no_connect"))
    )
    (net (code "86") (name "unconnected-(U6A-PM5{slash}T4CCP1{slash}TMPR2{slash}U0DCD-Pad73)") (class "Default")
      (node (ref "U6") (pin "73") (pinfunction "PM5/T4CCP1/TMPR2/U0DCD_73") (pintype "bidirectional+no_connect"))
    )
    (net (code "87") (name "unconnected-(U6A-PM6{slash}T5CCP0{slash}TMPR1{slash}U0DSR-Pad72)") (class "Default")
      (node (ref "U6") (pin "72") (pinfunction "PM6/T5CCP0/TMPR1/U0DSR_72") (pintype "bidirectional+no_connect"))
    )
    (net (code "88") (name "unconnected-(U6A-PM7{slash}T5CCP1{slash}TMPR0{slash}U0RI-Pad71)") (class "Default")
      (node (ref "U6") (pin "71") (pinfunction "PM7/T5CCP1/TMPR0/U0RI_71") (pintype "bidirectional+no_connect"))
    )
    (net (code "89") (name "unconnected-(U6A-PN0{slash}U1RTS-Pad107)") (class "Default")
      (node (ref "U6") (pin "107") (pinfunction "PN0/U1RTS_107") (pintype "bidirectional+no_connect"))
    )
    (net (code "90") (name "unconnected-(U6A-PN1{slash}U1CTS-Pad108)") (class "Default")
      (node (ref "U6") (pin "108") (pinfunction "PN1/U1CTS_108") (pintype "bidirectional+no_connect"))
    )
    (net (code "91") (name "unconnected-(U6A-PN2{slash}EPI0S29{slash}U1DCD{slash}U2RTS-Pad109)") (class "Default")
      (node (ref "U6") (pin "109") (pinfunction "PN2/EPI0S29/U1DCD/U2RTS_109") (pintype "bidirectional+no_connect"))
    )
    (net (code "92") (name "unconnected-(U6A-PN3{slash}EPI0S30{slash}U1DSR{slash}U2CTS-Pad110)") (class "Default")
      (node (ref "U6") (pin "110") (pinfunction "PN3/EPI0S30/U1DSR/U2CTS_110") (pintype "bidirectional+no_connect"))
    )
    (net (code "93") (name "unconnected-(U6A-PN4{slash}EPI0S34{slash}I2C2SDA{slash}U1DTR{slash}U3RTS-Pad111)") (class "Default")
      (node (ref "U6") (pin "111") (pinfunction "PN4/EPI0S34/I2C2SDA/U1DTR/U3RTS_111") (pintype "bidirectional+no_connect"))
    )
    (net (code "94") (name "unconnected-(U6A-PN5{slash}EPI0S35{slash}I2C2SCL{slash}U1RI{slash}U3CTS-Pad112)") (class "Default")
      (node (ref "U6") (pin "112") (pinfunction "PN5/EPI0S35/I2C2SCL/U1RI/U3CTS_112") (pintype "bidirectional+no_connect"))
    )
    (net (code "95") (name "unconnected-(U6A-PP0{slash}C2+{slash}SSI3XDAT2{slash}U6RX-Pad118)") (class "Default")
      (node (ref "U6") (pin "118") (pinfunction "PP0/C2+/SSI3XDAT2/U6RX_118") (pintype "bidirectional+no_connect"))
    )
    (net (code "96") (name "unconnected-(U6A-PP1{slash}C2-{slash}SSI3XDAT3{slash}U6TX-Pad119)") (class "Default")
      (node (ref "U6") (pin "119") (pinfunction "PP1/C2-/SSI3XDAT3/U6TX_119") (pintype "bidirectional+no_connect"))
    )
    (net (code "97") (name "unconnected-(U6A-PP2{slash}EPI0S29{slash}U0DTR{slash}USB0NXT-Pad103)") (class "Default")
      (node (ref "U6") (pin "103") (pinfunction "PP2/EPI0S29/U0DTR/USB0NXT_103") (pintype "bidirectional+no_connect"))
    )
    (net (code "98") (name "unconnected-(U6A-PP3{slash}EPI0S30{slash}RTCCLK{slash}U0DCD{slash}U1CTS{slash}USB0DIR-Pad104)") (class "Default")
      (node (ref "U6") (pin "104") (pinfunction "PP3/EPI0S30/RTCCLK/U0DCD/U1CTS/USB0DIR_104") (pintype "bidirectional+no_connect"))
    )
    (net (code "99") (name "unconnected-(U6A-PP4{slash}U0DSR{slash}U3RTS{slash}USB0D7-Pad105)") (class "Default")
      (node (ref "U6") (pin "105") (pinfunction "PP4/U0DSR/U3RTS/USB0D7_105") (pintype "bidirectional+no_connect"))
    )
    (net (code "100") (name "unconnected-(U6A-PP5{slash}I2C2SCL{slash}U3CTS{slash}USB0D6-Pad106)") (class "Default")
      (node (ref "U6") (pin "106") (pinfunction "PP5/I2C2SCL/U3CTS/USB0D6_106") (pintype "bidirectional+no_connect"))
    )
    (net (code "101") (name "unconnected-(U6A-PQ0{slash}EPI0S20{slash}SSI3CLK-Pad5)") (class "Default")
      (node (ref "U6") (pin "5") (pinfunction "PQ0/EPI0S20/SSI3CLK_5") (pintype "bidirectional+no_connect"))
    )
    (net (code "102") (name "unconnected-(U6A-PQ1{slash}EPI0S21{slash}SSI3FSS-Pad6)") (class "Default")
      (node (ref "U6") (pin "6") (pinfunction "PQ1/EPI0S21/SSI3FSS_6") (pintype "bidirectional+no_connect"))
    )
    (net (code "103") (name "unconnected-(U6A-PQ2{slash}EPI0S22{slash}SSI3XDAT0-Pad11)") (class "Default")
      (node (ref "U6") (pin "11") (pinfunction "PQ2/EPI0S22/SSI3XDAT0_11") (pintype "bidirectional+no_connect"))
    )
    (net (code "104") (name "unconnected-(U6A-PQ3{slash}EPI0S23{slash}SSI3XDAT1-Pad27)") (class "Default")
      (node (ref "U6") (pin "27") (pinfunction "PQ3/EPI0S23/SSI3XDAT1_27") (pintype "bidirectional+no_connect"))
    )
    (net (code "105") (name "unconnected-(U6A-PQ4{slash}DIVSCLK{slash}U1RX-Pad102)") (class "Default")
      (node (ref "U6") (pin "102") (pinfunction "PQ4/DIVSCLK/U1RX_102") (pintype "bidirectional+no_connect"))
    )
    (net (code "106") (name "unconnected-(U6B-EN0RXIN-Pad53)") (class "Default")
      (node (ref "U6") (pin "53") (pinfunction "EN0RXIN_53") (pintype "input+no_connect"))
    )
    (net (code "107") (name "unconnected-(U6B-EN0RXIP-Pad54)") (class "Default")
      (node (ref "U6") (pin "54") (pinfunction "EN0RXIP_54") (pintype "input+no_connect"))
    )
    (net (code "108") (name "unconnected-(U6B-EN0TXON-Pad56)") (class "Default")
      (node (ref "U6") (pin "56") (pinfunction "EN0TXON_56") (pintype "output+no_connect"))
    )
    (net (code "109") (name "unconnected-(U6B-EN0TXOP-Pad57)") (class "Default")
      (node (ref "U6") (pin "57") (pinfunction "EN0TXOP_57") (pintype "output+no_connect"))
    )
    (net (code "110") (name "unconnected-(U6B-XOSC1-Pad67)") (class "Default")
      (node (ref "U6") (pin "67") (pinfunction "XOSC1_67") (pintype "passive+no_connect"))
    )
    (net (code "111") (name "unconnected-(U6B-~{HIB}-Pad65)") (class "Default")
      (node (ref "U6") (pin "65") (pinfunction "~{HIB}_65") (pintype "output+no_connect"))
    )
    (net (code "112") (name "unconnected-(U7-NC-Pad3)") (class "Default")
      (node (ref "U7") (pin "3") (pinfunction "NC_3") (pintype "passive+no_connect"))
    )
  )
)
